# mkr1000_backpack.net
KiCad netlist of a schematic drawn in EAGLE
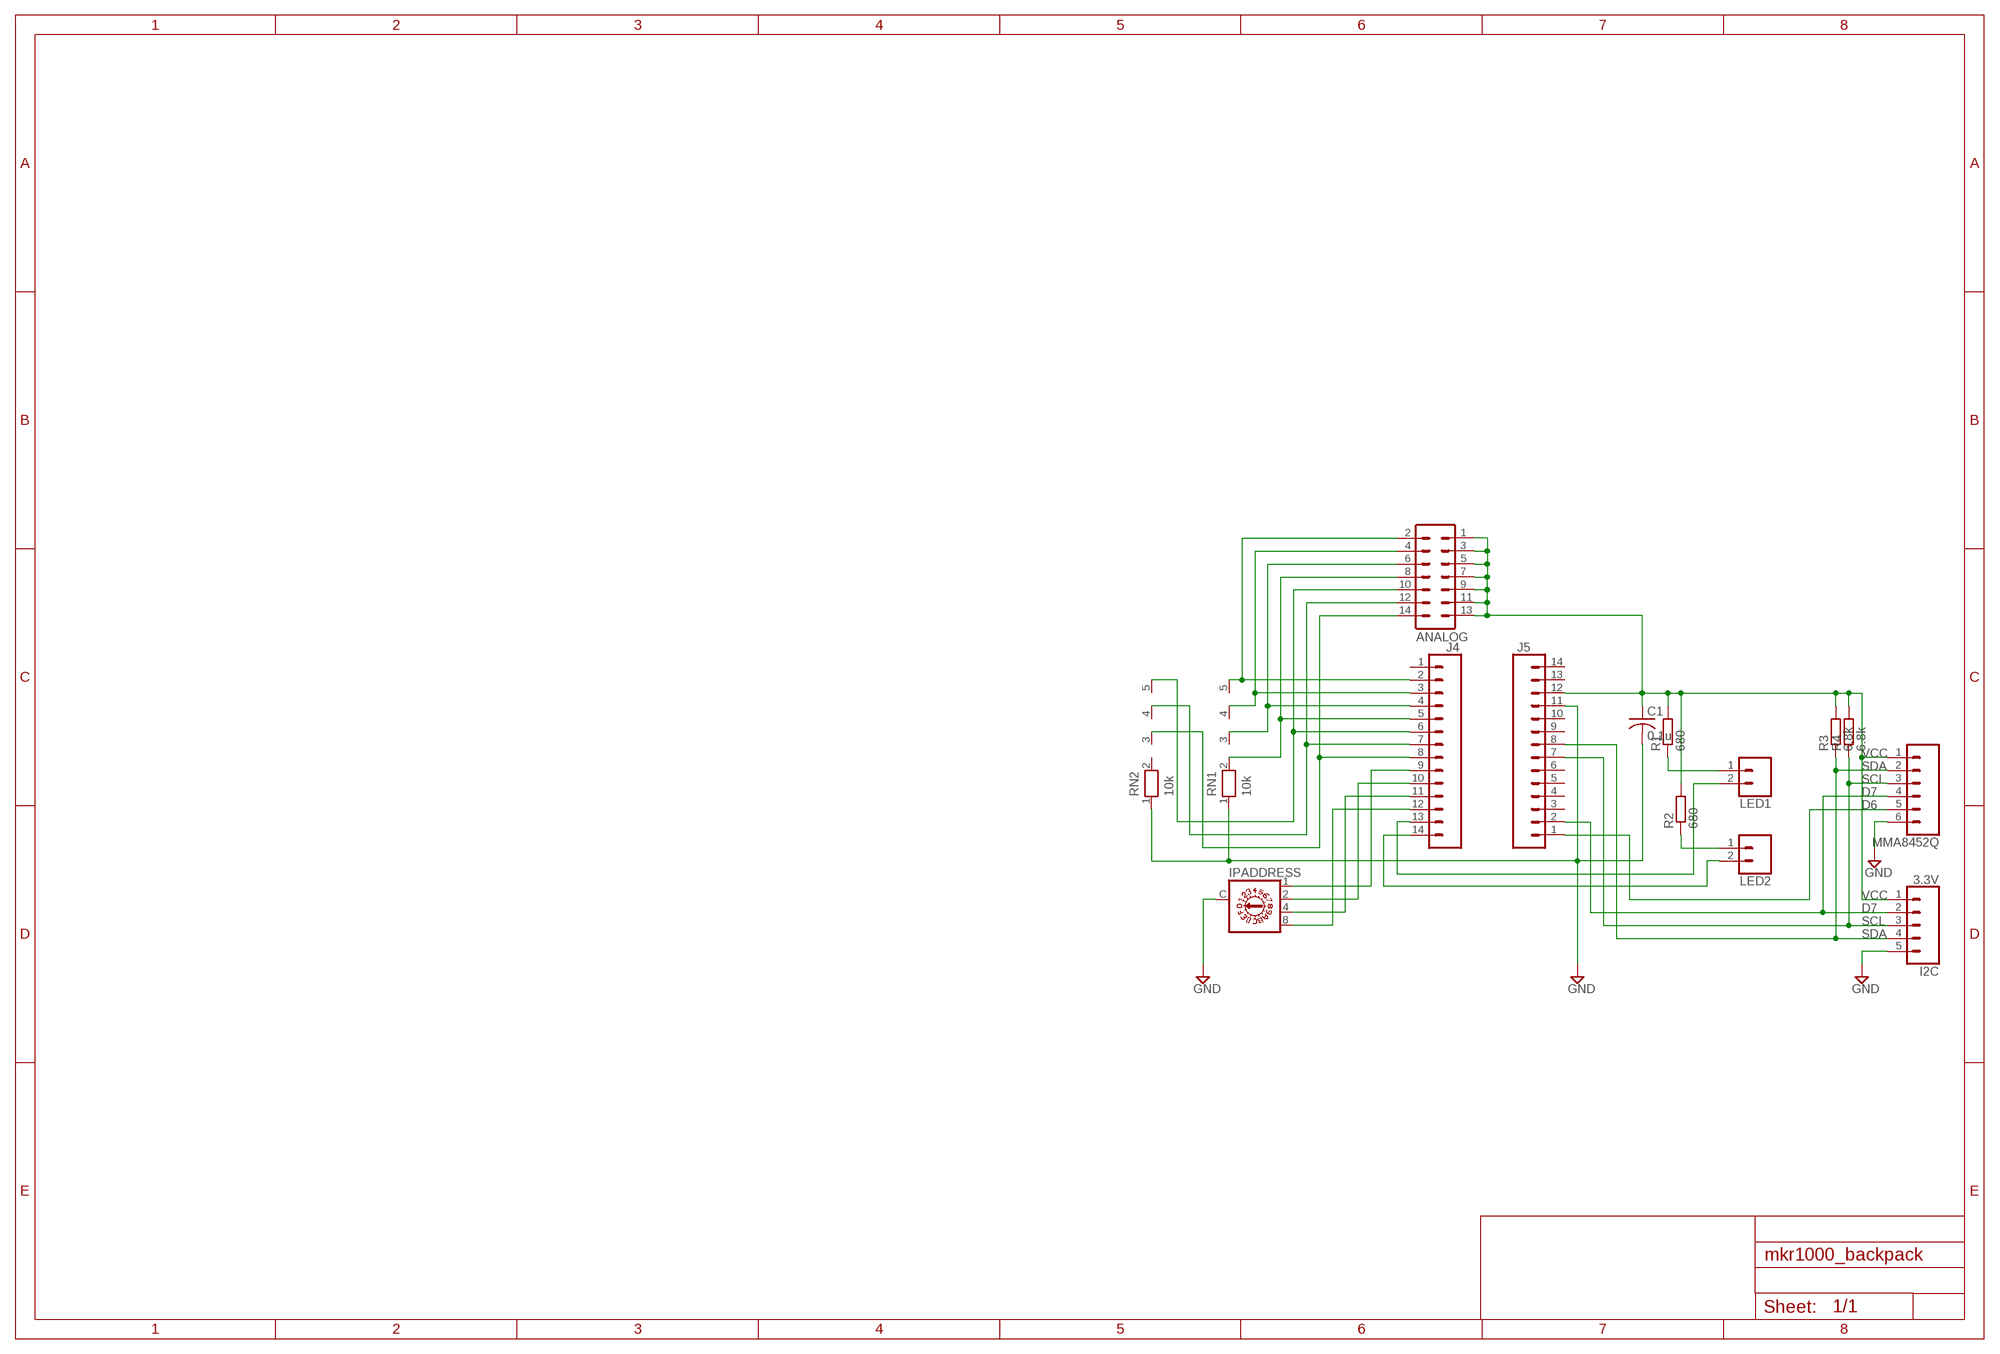
[diagram p0: schematic, sheet 1]

(export (version "E")
  (design (tool "Eeschema 10.0.6"))
  (components
    (comp (ref "ANALOG")
      (value "ML14L")
      (footprint "eagle-import:ML14L")
      (libsource (lib "eagle-import") (part "ML14L"))
    )
    (comp (ref "C1")
      (value "0.1u")
      (footprint "eagle-import:C025-025X050")
      (libsource (lib "eagle-import") (part "C-US025-025X050"))
    )
    (comp (ref "I2C")
      (value "3.3V")
      (footprint "eagle-import:1X05_1MM")
      (libsource (lib "eagle-import") (part "CONN_05SMD"))
    )
    (comp (ref "IPADDRESS")
      (value "A1353HEX")
      (footprint "eagle-import:A1353HEX")
      (libsource (lib "eagle-import") (part "A1353HEX"))
    )
    (comp (ref "J4")
      (value "DNP")
      (footprint "eagle-import:1X14")
      (libsource (lib "eagle-import") (part "CONN_14"))
    )
    (comp (ref "J5")
      (value "DNP")
      (footprint "eagle-import:1X14")
      (libsource (lib "eagle-import") (part "CONN_14"))
    )
    (comp (ref "LED1")
      (value "CONN_02-JST-2-PTH-NO_SILK")
      (footprint "eagle-import:JST-2-PTH-NS")
      (libsource (lib "eagle-import") (part "CONN_02-JST-2-PTH-NO_SILK"))
    )
    (comp (ref "LED2")
      (value "CONN_02-JST-2-PTH-NO_SILK")
      (footprint "eagle-import:JST-2-PTH-NS")
      (libsource (lib "eagle-import") (part "CONN_02-JST-2-PTH-NO_SILK"))
    )
    (comp (ref "MMA8452Q")
      (value "CONN_06NO_SILK_FEMALE_PTH")
      (footprint "eagle-import:1X06_NO_SILK")
      (libsource (lib "eagle-import") (part "CONN_06NO_SILK_FEMALE_PTH"))
    )
    (comp (ref "R1")
      (value "680")
      (footprint "eagle-import:0204_5")
      (libsource (lib "eagle-import") (part "R-EU_0204/5"))
    )
    (comp (ref "R2")
      (value "680")
      (footprint "eagle-import:0204_5")
      (libsource (lib "eagle-import") (part "R-EU_0204/5"))
    )
    (comp (ref "R3")
      (value "6.8k")
      (footprint "eagle-import:0204_5")
      (libsource (lib "eagle-import") (part "R-EU_0204/5"))
    )
    (comp (ref "R4")
      (value "6.8k")
      (footprint "eagle-import:0204_5")
      (libsource (lib "eagle-import") (part "R-EU_0204/5"))
    )
    (comp (ref "RN1")
      (value "10k")
      (footprint "eagle-import:RN-5")
      (libsource (lib "eagle-import") (part "RN04"))
    )
    (comp (ref "RN2")
      (value "10k")
      (footprint "eagle-import:RN-5")
      (libsource (lib "eagle-import") (part "RN04"))
    )
  )
  (nets
    (net (code "1") (name "/D6") (class "Default")
      (node (ref "J5") (pin "1") (pinfunction "1_1") (pintype "passive"))
      (node (ref "MMA8452Q") (pin "5") (pinfunction "5_5") (pintype "passive"))
    )
    (net (code "2") (name "/D7") (class "Default")
      (node (ref "I2C") (pin "2") (pinfunction "2_2") (pintype "passive"))
      (node (ref "J5") (pin "2") (pinfunction "2_2") (pintype "passive"))
      (node (ref "MMA8452Q") (pin "4") (pinfunction "4_4") (pintype "passive"))
    )
    (net (code "3") (name "/SCL") (class "Default")
      (node (ref "I2C") (pin "3") (pinfunction "3_3") (pintype "passive"))
      (node (ref "J5") (pin "7") (pinfunction "7_7") (pintype "passive"))
      (node (ref "MMA8452Q") (pin "3") (pinfunction "3_3") (pintype "passive"))
      (node (ref "R4") (pin "1") (pinfunction "1_1") (pintype "passive"))
    )
    (net (code "4") (name "/SDA") (class "Default")
      (node (ref "I2C") (pin "4") (pinfunction "4_4") (pintype "passive"))
      (node (ref "J5") (pin "8") (pinfunction "8_8") (pintype "passive"))
      (node (ref "MMA8452Q") (pin "2") (pinfunction "2_2") (pintype "passive"))
      (node (ref "R3") (pin "1") (pinfunction "1_1") (pintype "passive"))
    )
    (net (code "5") (name "/VCC") (class "Default")
      (node (ref "ANALOG") (pin "1") (pinfunction "1_1") (pintype "passive"))
      (node (ref "ANALOG") (pin "11") (pinfunction "11_11") (pintype "passive"))
      (node (ref "ANALOG") (pin "13") (pinfunction "13_13") (pintype "passive"))
      (node (ref "ANALOG") (pin "3") (pinfunction "3_3") (pintype "passive"))
      (node (ref "ANALOG") (pin "5") (pinfunction "5_5") (pintype "passive"))
      (node (ref "ANALOG") (pin "7") (pinfunction "7_7") (pintype "passive"))
      (node (ref "ANALOG") (pin "9") (pinfunction "9_9") (pintype "passive"))
      (node (ref "C1") (pin "1") (pinfunction "1_1") (pintype "passive"))
      (node (ref "I2C") (pin "1") (pinfunction "1_1") (pintype "passive"))
      (node (ref "J5") (pin "12") (pinfunction "12_12") (pintype "passive"))
      (node (ref "MMA8452Q") (pin "1") (pinfunction "1_1") (pintype "passive"))
      (node (ref "R1") (pin "2") (pinfunction "2_2") (pintype "passive"))
      (node (ref "R2") (pin "2") (pinfunction "2_2") (pintype "passive"))
      (node (ref "R3") (pin "2") (pinfunction "2_2") (pintype "passive"))
      (node (ref "R4") (pin "2") (pinfunction "2_2") (pintype "passive"))
    )
    (net (code "6") (name "GND") (class "Default")
      (node (ref "C1") (pin "2") (pinfunction "2_2") (pintype "passive"))
      (node (ref "I2C") (pin "5") (pinfunction "5_5") (pintype "passive"))
      (node (ref "IPADDRESS") (pin "C") (pinfunction "C_C") (pintype "passive"))
      (node (ref "J5") (pin "11") (pinfunction "11_11") (pintype "passive"))
      (node (ref "MMA8452Q") (pin "6") (pinfunction "6_6") (pintype "passive"))
      (node (ref "RN1") (pin "1") (pinfunction "1_1") (pintype "passive"))
      (node (ref "RN2") (pin "1") (pinfunction "1_1") (pintype "passive"))
    )
    (net (code "7") (name "Net-(ANALOG-Pad2)") (class "Default")
      (node (ref "ANALOG") (pin "2") (pinfunction "2_2") (pintype "passive"))
      (node (ref "J4") (pin "2") (pinfunction "2_2") (pintype "passive"))
      (node (ref "RN1") (pin "5") (pinfunction "5_5") (pintype "passive"))
    )
    (net (code "8") (name "Net-(ANALOG-Pad4)") (class "Default")
      (node (ref "ANALOG") (pin "4") (pinfunction "4_4") (pintype "passive"))
      (node (ref "J4") (pin "3") (pinfunction "3_3") (pintype "passive"))
      (node (ref "RN1") (pin "4") (pinfunction "4_4") (pintype "passive"))
    )
    (net (code "9") (name "Net-(ANALOG-Pad6)") (class "Default")
      (node (ref "ANALOG") (pin "6") (pinfunction "6_6") (pintype "passive"))
      (node (ref "J4") (pin "4") (pinfunction "4_4") (pintype "passive"))
      (node (ref "RN1") (pin "3") (pinfunction "3_3") (pintype "passive"))
    )
    (net (code "10") (name "Net-(ANALOG-Pad8)") (class "Default")
      (node (ref "ANALOG") (pin "8") (pinfunction "8_8") (pintype "passive"))
      (node (ref "J4") (pin "5") (pinfunction "5_5") (pintype "passive"))
      (node (ref "RN1") (pin "2") (pinfunction "2_2") (pintype "passive"))
    )
    (net (code "11") (name "Net-(ANALOG-Pad10)") (class "Default")
      (node (ref "ANALOG") (pin "10") (pinfunction "10_10") (pintype "passive"))
      (node (ref "J4") (pin "6") (pinfunction "6_6") (pintype "passive"))
      (node (ref "RN2") (pin "5") (pinfunction "5_5") (pintype "passive"))
    )
    (net (code "12") (name "Net-(ANALOG-Pad12)") (class "Default")
      (node (ref "ANALOG") (pin "12") (pinfunction "12_12") (pintype "passive"))
      (node (ref "J4") (pin "7") (pinfunction "7_7") (pintype "passive"))
      (node (ref "RN2") (pin "4") (pinfunction "4_4") (pintype "passive"))
    )
    (net (code "13") (name "Net-(ANALOG-Pad14)") (class "Default")
      (node (ref "ANALOG") (pin "14") (pinfunction "14_14") (pintype "passive"))
      (node (ref "J4") (pin "8") (pinfunction "8_8") (pintype "passive"))
      (node (ref "RN2") (pin "3") (pinfunction "3_3") (pintype "passive"))
    )
    (net (code "14") (name "Net-(IPADDRESS-Pad1)") (class "Default")
      (node (ref "IPADDRESS") (pin "1") (pinfunction "1_1") (pintype "passive"))
      (node (ref "J4") (pin "9") (pinfunction "9_9") (pintype "passive"))
    )
    (net (code "15") (name "Net-(IPADDRESS-Pad2)") (class "Default")
      (node (ref "IPADDRESS") (pin "2") (pinfunction "2_2") (pintype "passive"))
      (node (ref "J4") (pin "10") (pinfunction "10_10") (pintype "passive"))
    )
    (net (code "16") (name "Net-(IPADDRESS-Pad4)") (class "Default")
      (node (ref "IPADDRESS") (pin "4") (pinfunction "4_4") (pintype "passive"))
      (node (ref "J4") (pin "11") (pinfunction "11_11") (pintype "passive"))
    )
    (net (code "17") (name "Net-(IPADDRESS-Pad8)") (class "Default")
      (node (ref "IPADDRESS") (pin "8") (pinfunction "8_8") (pintype "passive"))
      (node (ref "J4") (pin "12") (pinfunction "12_12") (pintype "passive"))
    )
    (net (code "18") (name "Net-(J4-Pad13)") (class "Default")
      (node (ref "J4") (pin "13") (pinfunction "13_13") (pintype "passive"))
      (node (ref "LED1") (pin "2") (pinfunction "2_2") (pintype "passive"))
    )
    (net (code "19") (name "Net-(J4-Pad14)") (class "Default")
      (node (ref "J4") (pin "14") (pinfunction "14_14") (pintype "passive"))
      (node (ref "LED2") (pin "2") (pinfunction "2_2") (pintype "passive"))
    )
    (net (code "20") (name "Net-(LED1-Pad1)") (class "Default")
      (node (ref "LED1") (pin "1") (pinfunction "1_1") (pintype "passive"))
      (node (ref "R1") (pin "1") (pinfunction "1_1") (pintype "passive"))
    )
    (net (code "21") (name "Net-(LED2-Pad1)") (class "Default")
      (node (ref "LED2") (pin "1") (pinfunction "1_1") (pintype "passive"))
      (node (ref "R2") (pin "1") (pinfunction "1_1") (pintype "passive"))
    )
    (net (code "22") (name "unconnected-(J4-Pad1)") (class "Default")
      (node (ref "J4") (pin "1") (pinfunction "1_1") (pintype "passive"))
    )
    (net (code "23") (name "unconnected-(J5-Pad3)") (class "Default")
      (node (ref "J5") (pin "3") (pinfunction "3_3") (pintype "passive"))
    )
    (net (code "24") (name "unconnected-(J5-Pad4)") (class "Default")
      (node (ref "J5") (pin "4") (pinfunction "4_4") (pintype "passive"))
    )
    (net (code "25") (name "unconnected-(J5-Pad5)") (class "Default")
      (node (ref "J5") (pin "5") (pinfunction "5_5") (pintype "passive"))
    )
    (net (code "26") (name "unconnected-(J5-Pad6)") (class "Default")
      (node (ref "J5") (pin "6") (pinfunction "6_6") (pintype "passive"))
    )
    (net (code "27") (name "unconnected-(J5-Pad9)") (class "Default")
      (node (ref "J5") (pin "9") (pinfunction "9_9") (pintype "passive"))
    )
    (net (code "28") (name "unconnected-(J5-Pad10)") (class "Default")
      (node (ref "J5") (pin "10") (pinfunction "10_10") (pintype "passive"))
    )
    (net (code "29") (name "unconnected-(J5-Pad13)") (class "Default")
      (node (ref "J5") (pin "13") (pinfunction "13_13") (pintype "passive"))
    )
    (net (code "30") (name "unconnected-(J5-Pad14)") (class "Default")
      (node (ref "J5") (pin "14") (pinfunction "14_14") (pintype "passive"))
    )
    (net (code "31") (name "unconnected-(RN2-Pad2)") (class "Default")
      (node (ref "RN2") (pin "2") (pinfunction "2_2") (pintype "passive"))
    )
  )
)
